# attiny-breakout.net
KiCad netlist of a schematic drawn in EAGLE
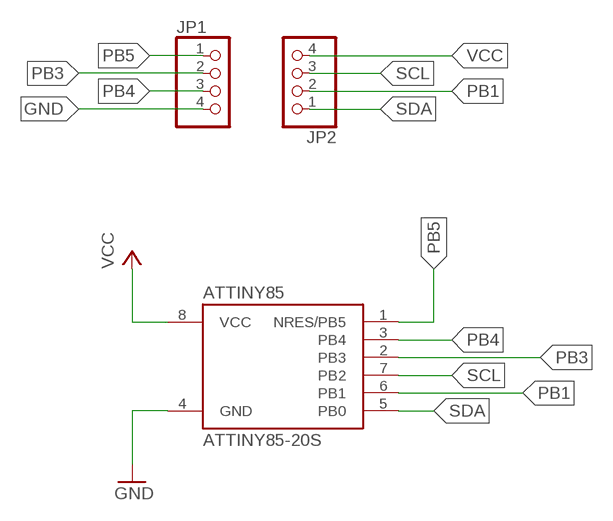
[diagram p0: schematic, sheet 1]

(export (version "E")
  (design (tool "Eeschema 10.0.6"))
  (components
    (comp (ref "ATTINY85")
      (value "ATTINY85-20S")
      (footprint "eagle-import:SOIC8_EIAJ_208MIL")
      (libsource (lib "eagle-import") (part "ATTINY85S-20"))
    )
    (comp (ref "JP1")
      (value "PINHD-1X4")
      (footprint "eagle-import:1X04")
      (libsource (lib "eagle-import") (part "PINHD-1X4"))
    )
    (comp (ref "JP2")
      (value "PINHD-1X4")
      (footprint "eagle-import:1X04")
      (libsource (lib "eagle-import") (part "PINHD-1X4"))
    )
  )
  (nets
    (net (code "1") (name "GND") (class "Default")
      (node (ref "ATTINY85") (pin "4") (pinfunction "GND_4") (pintype "power_in"))
      (node (ref "JP1") (pin "4") (pinfunction "4_4") (pintype "passive"))
    )
    (net (code "2") (name "PB1") (class "Default")
      (node (ref "ATTINY85") (pin "6") (pinfunction "PB1_6") (pintype "bidirectional"))
      (node (ref "JP2") (pin "2") (pinfunction "2_2") (pintype "passive"))
    )
    (net (code "3") (name "PB3") (class "Default")
      (node (ref "ATTINY85") (pin "2") (pinfunction "PB3_2") (pintype "bidirectional"))
      (node (ref "JP1") (pin "2") (pinfunction "2_2") (pintype "passive"))
    )
    (net (code "4") (name "PB4") (class "Default")
      (node (ref "ATTINY85") (pin "3") (pinfunction "PB4_3") (pintype "bidirectional"))
      (node (ref "JP1") (pin "3") (pinfunction "3_3") (pintype "passive"))
    )
    (net (code "5") (name "PB5") (class "Default")
      (node (ref "ATTINY85") (pin "1") (pinfunction "NRES/PB5_1") (pintype "bidirectional"))
      (node (ref "JP1") (pin "1") (pinfunction "1_1") (pintype "passive"))
    )
    (net (code "6") (name "SCL") (class "Default")
      (node (ref "ATTINY85") (pin "7") (pinfunction "PB2_7") (pintype "bidirectional"))
      (node (ref "JP2") (pin "3") (pinfunction "3_3") (pintype "passive"))
    )
    (net (code "7") (name "SDA") (class "Default")
      (node (ref "ATTINY85") (pin "5") (pinfunction "PB0_5") (pintype "bidirectional"))
      (node (ref "JP2") (pin "1") (pinfunction "1_1") (pintype "passive"))
    )
    (net (code "8") (name "VCC") (class "Default")
      (node (ref "ATTINY85") (pin "8") (pinfunction "VCC_8") (pintype "power_in"))
      (node (ref "JP2") (pin "4") (pinfunction "4_4") (pintype "passive"))
    )
  )
)
